# BigButtons.net
KiCad netlist of a schematic drawn in Altium Designer
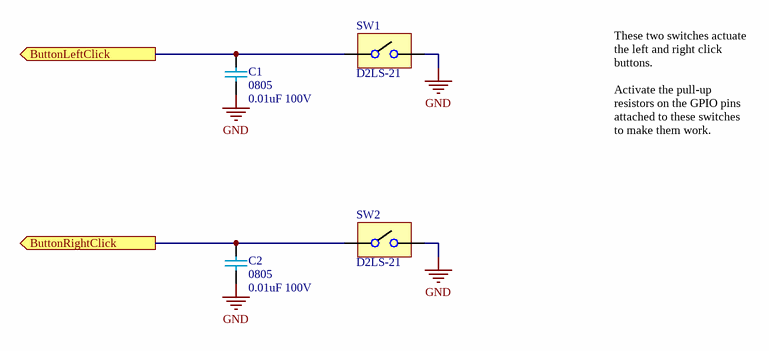
[diagram p0: BigButtons.SchDoc]

(export (version "E")
  (design (tool "Eeschema 10.0.6"))
  (components
    (comp (ref "C1")
      (value "0805")
      (footprint "0805")
      (description "0805, X5R or better")
      (fields (field (name "ALTIUM_VALUE") "0.01uF 100V"))
      (libsource (lib "Chip_Passives") (part "Cap 0.01uF 100V"))
    )
    (comp (ref "C2")
      (value "0805")
      (footprint "0805")
      (description "0805, X5R or better")
      (fields (field (name "ALTIUM_VALUE") "0.01uF 100V"))
      (libsource (lib "Chip_Passives") (part "Cap 0.01uF 100V"))
    )
    (comp (ref "SW1")
      (value "D2LS-21")
      (footprint "D2LS-21")
      (description "Compact Surface-mounting Switch for long durability")
      (libsource (lib "Switches") (part "D2LS-21"))
    )
    (comp (ref "SW2")
      (value "D2LS-21")
      (footprint "D2LS-21")
      (description "Compact Surface-mounting Switch for long durability")
      (libsource (lib "Switches") (part "D2LS-21"))
    )
  )
  (nets
    (net (code "1") (name "/ButtonLeftClick") (class "Default")
      (node (ref "C1") (pin "2") (pinfunction "2_2") (pintype "passive"))
      (node (ref "SW1") (pin "A") (pinfunction "A_A") (pintype "passive"))
    )
    (net (code "2") (name "/ButtonRightClick") (class "Default")
      (node (ref "C2") (pin "2") (pinfunction "2_2") (pintype "passive"))
      (node (ref "SW2") (pin "A") (pinfunction "A_A") (pintype "passive"))
    )
    (net (code "3") (name "GND") (class "Default")
      (node (ref "C1") (pin "1") (pinfunction "1_1") (pintype "passive"))
      (node (ref "C2") (pin "1") (pinfunction "1_1") (pintype "passive"))
      (node (ref "SW1") (pin "B") (pinfunction "B_B") (pintype "passive"))
      (node (ref "SW2") (pin "B") (pinfunction "B_B") (pintype "passive"))
    )
  )
)
